# Modem1.net
KiCad netlist of a schematic drawn in Altium Designer
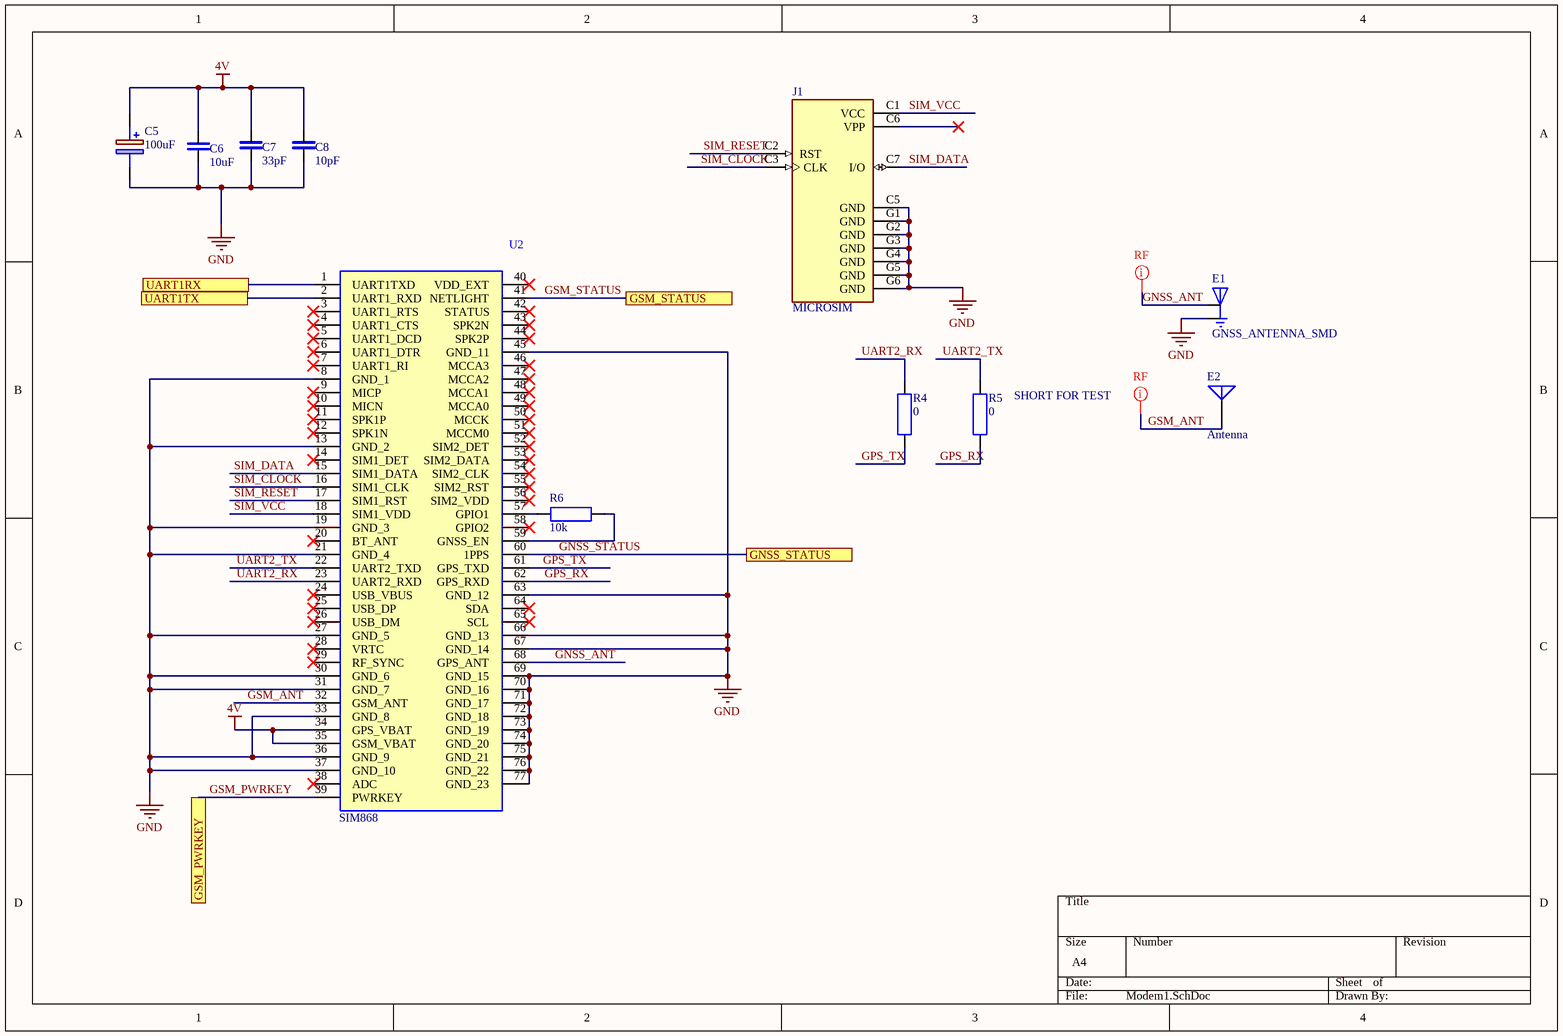
[diagram p0: Modem1.SchDoc]

(export (version "E")
  (design (tool "Eeschema 10.0.6"))
  (components
    (comp (ref "C5")
      (value "100uF")
      (footprint "TANTALUM_CAP_0805")
      (description "T491C107K016AT")
      (fields (field (name "MOUSER PART NUMBER") "80-T491C107K016AT"))
      (libsource (lib "Passive_Components") (part "SMT_TANTALUM_CAP"))
    )
    (comp (ref "C6")
      (value "10uF")
      (footprint "CAP_0805")
      (fields (field (name "MP") "LD051A270KAB2A"))
      (libsource (lib "Passive_Components") (part "SMT_CAP"))
    )
    (comp (ref "C7")
      (value "33pF")
      (footprint "CAP_0805")
      (fields (field (name "MP") "LD051A270KAB2A"))
      (libsource (lib "Passive_Components") (part "SMT_CAP"))
    )
    (comp (ref "C8")
      (value "10pF")
      (footprint "CAP_0805")
      (fields (field (name "MP") "LD051A270KAB2A"))
      (libsource (lib "Passive_Components") (part "SMT_CAP"))
    )
    (comp (ref "E1")
      (value "GNSS_ANTENNA_SMD")
      (footprint "GNSS_ANTENNA_SMD")
      (description "Ceramic GNSS antenna 25*25 SMD")
      (fields (field (name "MF") "Linx") (field (name "MP") "ANT-GNSSCP-TH18L1"))
      (libsource (lib "Extras") (part "GNSS_ANTENNA_SMD"))
    )
    (comp (ref "E2")
      (value "Antenna")
      (footprint "PIN1")
      (description "Generic Antenna")
      (fields (field (name "PUBLISHER") "Altium Limited"))
      (libsource (lib "Miscellaneous Devices") (part "Antenna"))
    )
    (comp (ref "J1")
      (value "MICROSIM")
      (footprint "MICROSIM")
      (description "PART NR: 78646-3001")
      (fields (field (name "MP") "78646-3001") (field (name "MF") "Molex"))
      (libsource (lib "Extras") (part "MICROSIM"))
    )
    (comp (ref "R4")
      (value "0")
      (footprint "RES_0805")
      (fields
        (field (name "MP") "2-2176053-0")
        (field (name "TOLERANCE") "1%")
        (field (name "MF") "TE Connectivity")
      )
      (libsource (lib "Passive_Components") (part "SMT_RES"))
    )
    (comp (ref "R5")
      (value "0")
      (footprint "RES_0805")
      (fields
        (field (name "MP") "2-2176053-0")
        (field (name "TOLERANCE") "1%")
        (field (name "MF") "TE Connectivity")
      )
      (libsource (lib "Passive_Components") (part "SMT_RES"))
    )
    (comp (ref "R6")
      (value "10k")
      (footprint "RES_0805")
      (fields
        (field (name "MP") "2-2176053-0")
        (field (name "TOLERANCE") "1%")
        (field (name "MF") "TE Connectivity")
      )
      (libsource (lib "Passive_Components") (part "SMT_RES"))
    )
    (comp (ref "U2")
      (value "GPRS,GSM,GNSS Modem")
      (footprint "SIM868")
      (fields (field (name "MANUFACTURER_PART_NUMBER") "SIM868") (field (name "SYMBOLNAME_1") "SIM868"))
      (libsource (lib "IC") (part "SIM868"))
    )
  )
  (nets
    (net (code "1") (name "/GNSS_ANT") (class "Default")
      (node (ref "E1") (pin "1") (pinfunction "FEEDING_1") (pintype "passive"))
      (node (ref "U2") (pin "68") (pinfunction "GPS_ANT_68") (pintype "power_in"))
    )
    (net (code "2") (name "/GNSS_STATUS") (class "Default")
      (node (ref "U2") (pin "60") (pinfunction "1PPS_60") (pintype "power_in"))
    )
    (net (code "3") (name "/GPS_RX") (class "Default")
      (node (ref "R5") (pin "1") (pinfunction "1_1") (pintype "passive"))
      (node (ref "U2") (pin "62") (pinfunction "GPS_RXD_62") (pintype "power_in"))
    )
    (net (code "4") (name "/GPS_TX") (class "Default")
      (node (ref "R4") (pin "1") (pinfunction "1_1") (pintype "passive"))
      (node (ref "U2") (pin "61") (pinfunction "GPS_TXD_61") (pintype "power_in"))
    )
    (net (code "5") (name "/GSM_ANT") (class "Default")
      (node (ref "E2") (pin "1") (pinfunction "A_1") (pintype "passive"))
      (node (ref "U2") (pin "32") (pinfunction "GSM_ANT_32") (pintype "power_in"))
    )
    (net (code "6") (name "/GSM_PWRKEY") (class "Default")
      (node (ref "U2") (pin "39") (pinfunction "PWRKEY_39") (pintype "power_in"))
    )
    (net (code "7") (name "/GSM_STATUS") (class "Default")
      (node (ref "U2") (pin "41") (pinfunction "NETLIGHT_41") (pintype "power_in"))
    )
    (net (code "8") (name "/SIM_CLOCK") (class "Default")
      (node (ref "J1") (pin "C3") (pinfunction "CLK_C3") (pintype "input"))
      (node (ref "U2") (pin "16") (pinfunction "SIM1_CLK_16") (pintype "power_in"))
    )
    (net (code "9") (name "/SIM_DATA") (class "Default")
      (node (ref "J1") (pin "C7") (pinfunction "I/O_C7") (pintype "bidirectional"))
      (node (ref "U2") (pin "15") (pinfunction "SIM1_DATA_15") (pintype "power_in"))
    )
    (net (code "10") (name "/SIM_RESET") (class "Default")
      (node (ref "J1") (pin "C2") (pinfunction "RST_C2") (pintype "input"))
      (node (ref "U2") (pin "17") (pinfunction "SIM1_RST_17") (pintype "power_in"))
    )
    (net (code "11") (name "/SIM_VCC") (class "Default")
      (node (ref "J1") (pin "C1") (pinfunction "VCC_C1") (pintype "power_in"))
      (node (ref "U2") (pin "18") (pinfunction "SIM1_VDD_18") (pintype "power_in"))
    )
    (net (code "12") (name "/UART1RX") (class "Default")
      (node (ref "U2") (pin "1") (pinfunction "UART1TXD_1") (pintype "power_in"))
    )
    (net (code "13") (name "/UART1TX") (class "Default")
      (node (ref "U2") (pin "2") (pinfunction "UART1_RXD_2") (pintype "power_in"))
    )
    (net (code "14") (name "/UART2_RX") (class "Default")
      (node (ref "R4") (pin "2") (pinfunction "2_2") (pintype "passive"))
      (node (ref "U2") (pin "23") (pinfunction "UART2_RXD_23") (pintype "power_in"))
    )
    (net (code "15") (name "/UART2_TX") (class "Default")
      (node (ref "R5") (pin "2") (pinfunction "2_2") (pintype "passive"))
      (node (ref "U2") (pin "22") (pinfunction "UART2_TXD_22") (pintype "power_in"))
    )
    (net (code "16") (name "4V") (class "Default")
      (node (ref "C5") (pin "1") (pinfunction "+_1") (pintype "passive"))
      (node (ref "C6") (pin "2") (pinfunction "2_2") (pintype "passive"))
      (node (ref "C7") (pin "2") (pinfunction "2_2") (pintype "passive"))
      (node (ref "C8") (pin "2") (pinfunction "2_2") (pintype "passive"))
      (node (ref "U2") (pin "34") (pinfunction "GPS_VBAT_34") (pintype "power_in"))
      (node (ref "U2") (pin "35") (pinfunction "GSM_VBAT_35") (pintype "power_in"))
    )
    (net (code "17") (name "GND") (class "Default")
      (node (ref "C5") (pin "2") (pinfunction "-_2") (pintype "passive"))
      (node (ref "C6") (pin "1") (pinfunction "1_1") (pintype "passive"))
      (node (ref "C7") (pin "1") (pinfunction "1_1") (pintype "passive"))
      (node (ref "C8") (pin "1") (pinfunction "1_1") (pintype "passive"))
      (node (ref "E1") (pin "2") (pinfunction "GND_2") (pintype "power_in"))
      (node (ref "J1") (pin "C5") (pinfunction "GND_C5") (pintype "power_in"))
      (node (ref "J1") (pin "G1") (pinfunction "GND_G1") (pintype "power_in"))
      (node (ref "J1") (pin "G2") (pinfunction "GND_G2") (pintype "power_in"))
      (node (ref "J1") (pin "G3") (pinfunction "GND_G3") (pintype "power_in"))
      (node (ref "J1") (pin "G4") (pinfunction "GND_G4") (pintype "power_in"))
      (node (ref "J1") (pin "G5") (pinfunction "GND_G5") (pintype "power_in"))
      (node (ref "J1") (pin "G6") (pinfunction "GND_G6") (pintype "power_in"))
      (node (ref "U2") (pin "13") (pinfunction "GND_2_13") (pintype "power_in"))
      (node (ref "U2") (pin "19") (pinfunction "GND_3_19") (pintype "power_in"))
      (node (ref "U2") (pin "21") (pinfunction "GND_4_21") (pintype "power_in"))
      (node (ref "U2") (pin "27") (pinfunction "GND_5_27") (pintype "power_in"))
      (node (ref "U2") (pin "30") (pinfunction "GND_6_30") (pintype "power_in"))
      (node (ref "U2") (pin "31") (pinfunction "GND_7_31") (pintype "power_in"))
      (node (ref "U2") (pin "33") (pinfunction "GND_8_33") (pintype "power_in"))
      (node (ref "U2") (pin "36") (pinfunction "GND_9_36") (pintype "power_in"))
      (node (ref "U2") (pin "37") (pinfunction "GND_10_37") (pintype "power_in"))
      (node (ref "U2") (pin "45") (pinfunction "GND_11_45") (pintype "power_in"))
      (node (ref "U2") (pin "63") (pinfunction "GND_12_63") (pintype "power_in"))
      (node (ref "U2") (pin "66") (pinfunction "GND_13_66") (pintype "power_in"))
      (node (ref "U2") (pin "67") (pinfunction "GND_14_67") (pintype "power_in"))
      (node (ref "U2") (pin "69") (pinfunction "GND_15_69") (pintype "power_in"))
      (node (ref "U2") (pin "70") (pinfunction "GND_16_70") (pintype "power_in"))
      (node (ref "U2") (pin "71") (pinfunction "GND_17_71") (pintype "power_in"))
      (node (ref "U2") (pin "72") (pinfunction "GND_18_72") (pintype "power_in"))
      (node (ref "U2") (pin "73") (pinfunction "GND_19_73") (pintype "power_in"))
      (node (ref "U2") (pin "74") (pinfunction "GND_20_74") (pintype "power_in"))
      (node (ref "U2") (pin "75") (pinfunction "GND_21_75") (pintype "power_in"))
      (node (ref "U2") (pin "76") (pinfunction "GND_22_76") (pintype "power_in"))
      (node (ref "U2") (pin "77") (pinfunction "GND_23_77") (pintype "power_in"))
      (node (ref "U2") (pin "8") (pinfunction "GND_1_8") (pintype "power_in"))
    )
    (net (code "18") (name "Net-(U2-GNSS_EN)") (class "Default")
      (node (ref "R6") (pin "2") (pinfunction "2_2") (pintype "passive"))
      (node (ref "U2") (pin "59") (pinfunction "GNSS_EN_59") (pintype "power_in"))
    )
    (net (code "19") (name "Net-(U2-GPIO1)") (class "Default")
      (node (ref "R6") (pin "1") (pinfunction "1_1") (pintype "passive"))
      (node (ref "U2") (pin "57") (pinfunction "GPIO1_57") (pintype "power_in"))
    )
    (net (code "20") (name "unconnected-(J1-VPP-PadC6)") (class "Default")
      (node (ref "J1") (pin "C6") (pinfunction "VPP_C6") (pintype "power_in+no_connect"))
    )
    (net (code "21") (name "unconnected-(U2-ADC-Pad38)") (class "Default")
      (node (ref "U2") (pin "38") (pinfunction "ADC_38") (pintype "power_in+no_connect"))
    )
    (net (code "22") (name "unconnected-(U2-BT_ANT-Pad20)") (class "Default")
      (node (ref "U2") (pin "20") (pinfunction "BT_ANT_20") (pintype "power_in+no_connect"))
    )
    (net (code "23") (name "unconnected-(U2-GPIO2-Pad58)") (class "Default")
      (node (ref "U2") (pin "58") (pinfunction "GPIO2_58") (pintype "power_in+no_connect"))
    )
    (net (code "24") (name "unconnected-(U2-MCCA0-Pad49)") (class "Default")
      (node (ref "U2") (pin "49") (pinfunction "MCCA0_49") (pintype "power_in+no_connect"))
    )
    (net (code "25") (name "unconnected-(U2-MCCA1-Pad48)") (class "Default")
      (node (ref "U2") (pin "48") (pinfunction "MCCA1_48") (pintype "power_in+no_connect"))
    )
    (net (code "26") (name "unconnected-(U2-MCCA2-Pad47)") (class "Default")
      (node (ref "U2") (pin "47") (pinfunction "MCCA2_47") (pintype "power_in+no_connect"))
    )
    (net (code "27") (name "unconnected-(U2-MCCA3-Pad46)") (class "Default")
      (node (ref "U2") (pin "46") (pinfunction "MCCA3_46") (pintype "power_in+no_connect"))
    )
    (net (code "28") (name "unconnected-(U2-MCCK-Pad50)") (class "Default")
      (node (ref "U2") (pin "50") (pinfunction "MCCK_50") (pintype "power_in+no_connect"))
    )
    (net (code "29") (name "unconnected-(U2-MCCM0-Pad51)") (class "Default")
      (node (ref "U2") (pin "51") (pinfunction "MCCM0_51") (pintype "power_in+no_connect"))
    )
    (net (code "30") (name "unconnected-(U2-MICN-Pad10)") (class "Default")
      (node (ref "U2") (pin "10") (pinfunction "MICN_10") (pintype "power_in+no_connect"))
    )
    (net (code "31") (name "unconnected-(U2-MICP-Pad9)") (class "Default")
      (node (ref "U2") (pin "9") (pinfunction "MICP_9") (pintype "power_in+no_connect"))
    )
    (net (code "32") (name "unconnected-(U2-RF_SYNC-Pad29)") (class "Default")
      (node (ref "U2") (pin "29") (pinfunction "RF_SYNC_29") (pintype "power_in+no_connect"))
    )
    (net (code "33") (name "unconnected-(U2-SCL-Pad65)") (class "Default")
      (node (ref "U2") (pin "65") (pinfunction "SCL_65") (pintype "power_in+no_connect"))
    )
    (net (code "34") (name "unconnected-(U2-SDA-Pad64)") (class "Default")
      (node (ref "U2") (pin "64") (pinfunction "SDA_64") (pintype "power_in+no_connect"))
    )
    (net (code "35") (name "unconnected-(U2-SIM1_DET-Pad14)") (class "Default")
      (node (ref "U2") (pin "14") (pinfunction "SIM1_DET_14") (pintype "power_in+no_connect"))
    )
    (net (code "36") (name "unconnected-(U2-SIM2_CLK-Pad54)") (class "Default")
      (node (ref "U2") (pin "54") (pinfunction "SIM2_CLK_54") (pintype "power_in+no_connect"))
    )
    (net (code "37") (name "unconnected-(U2-SIM2_DATA-Pad53)") (class "Default")
      (node (ref "U2") (pin "53") (pinfunction "SIM2_DATA_53") (pintype "power_in+no_connect"))
    )
    (net (code "38") (name "unconnected-(U2-SIM2_DET-Pad52)") (class "Default")
      (node (ref "U2") (pin "52") (pinfunction "SIM2_DET_52") (pintype "power_in+no_connect"))
    )
    (net (code "39") (name "unconnected-(U2-SIM2_RST-Pad55)") (class "Default")
      (node (ref "U2") (pin "55") (pinfunction "SIM2_RST_55") (pintype "power_in+no_connect"))
    )
    (net (code "40") (name "unconnected-(U2-SIM2_VDD-Pad56)") (class "Default")
      (node (ref "U2") (pin "56") (pinfunction "SIM2_VDD_56") (pintype "power_in+no_connect"))
    )
    (net (code "41") (name "unconnected-(U2-SPK1N-Pad12)") (class "Default")
      (node (ref "U2") (pin "12") (pinfunction "SPK1N_12") (pintype "power_in+no_connect"))
    )
    (net (code "42") (name "unconnected-(U2-SPK1P-Pad11)") (class "Default")
      (node (ref "U2") (pin "11") (pinfunction "SPK1P_11") (pintype "power_in+no_connect"))
    )
    (net (code "43") (name "unconnected-(U2-SPK2N-Pad43)") (class "Default")
      (node (ref "U2") (pin "43") (pinfunction "SPK2N_43") (pintype "power_in+no_connect"))
    )
    (net (code "44") (name "unconnected-(U2-SPK2P-Pad44)") (class "Default")
      (node (ref "U2") (pin "44") (pinfunction "SPK2P_44") (pintype "power_in+no_connect"))
    )
    (net (code "45") (name "unconnected-(U2-STATUS-Pad42)") (class "Default")
      (node (ref "U2") (pin "42") (pinfunction "STATUS_42") (pintype "power_in+no_connect"))
    )
    (net (code "46") (name "unconnected-(U2-UART1_CTS-Pad4)") (class "Default")
      (node (ref "U2") (pin "4") (pinfunction "UART1_CTS_4") (pintype "power_in+no_connect"))
    )
    (net (code "47") (name "unconnected-(U2-UART1_DCD-Pad5)") (class "Default")
      (node (ref "U2") (pin "5") (pinfunction "UART1_DCD_5") (pintype "power_in+no_connect"))
    )
    (net (code "48") (name "unconnected-(U2-UART1_DTR-Pad6)") (class "Default")
      (node (ref "U2") (pin "6") (pinfunction "UART1_DTR_6") (pintype "power_in+no_connect"))
    )
    (net (code "49") (name "unconnected-(U2-UART1_RI-Pad7)") (class "Default")
      (node (ref "U2") (pin "7") (pinfunction "UART1_RI_7") (pintype "power_in+no_connect"))
    )
    (net (code "50") (name "unconnected-(U2-UART1_RTS-Pad3)") (class "Default")
      (node (ref "U2") (pin "3") (pinfunction "UART1_RTS_3") (pintype "power_in+no_connect"))
    )
    (net (code "51") (name "unconnected-(U2-USB_DM-Pad26)") (class "Default")
      (node (ref "U2") (pin "26") (pinfunction "USB_DM_26") (pintype "power_in+no_connect"))
    )
    (net (code "52") (name "unconnected-(U2-USB_DP-Pad25)") (class "Default")
      (node (ref "U2") (pin "25") (pinfunction "USB_DP_25") (pintype "power_in+no_connect"))
    )
    (net (code "53") (name "unconnected-(U2-USB_VBUS-Pad24)") (class "Default")
      (node (ref "U2") (pin "24") (pinfunction "USB_VBUS_24") (pintype "power_in+no_connect"))
    )
    (net (code "54") (name "unconnected-(U2-VDD_EXT-Pad40)") (class "Default")
      (node (ref "U2") (pin "40") (pinfunction "VDD_EXT_40") (pintype "power_in+no_connect"))
    )
    (net (code "55") (name "unconnected-(U2-VRTC-Pad28)") (class "Default")
      (node (ref "U2") (pin "28") (pinfunction "VRTC_28") (pintype "power_in+no_connect"))
    )
  )
)
